# SkyNetV3main-1.net
KiCad netlist of a schematic drawn in EAGLE
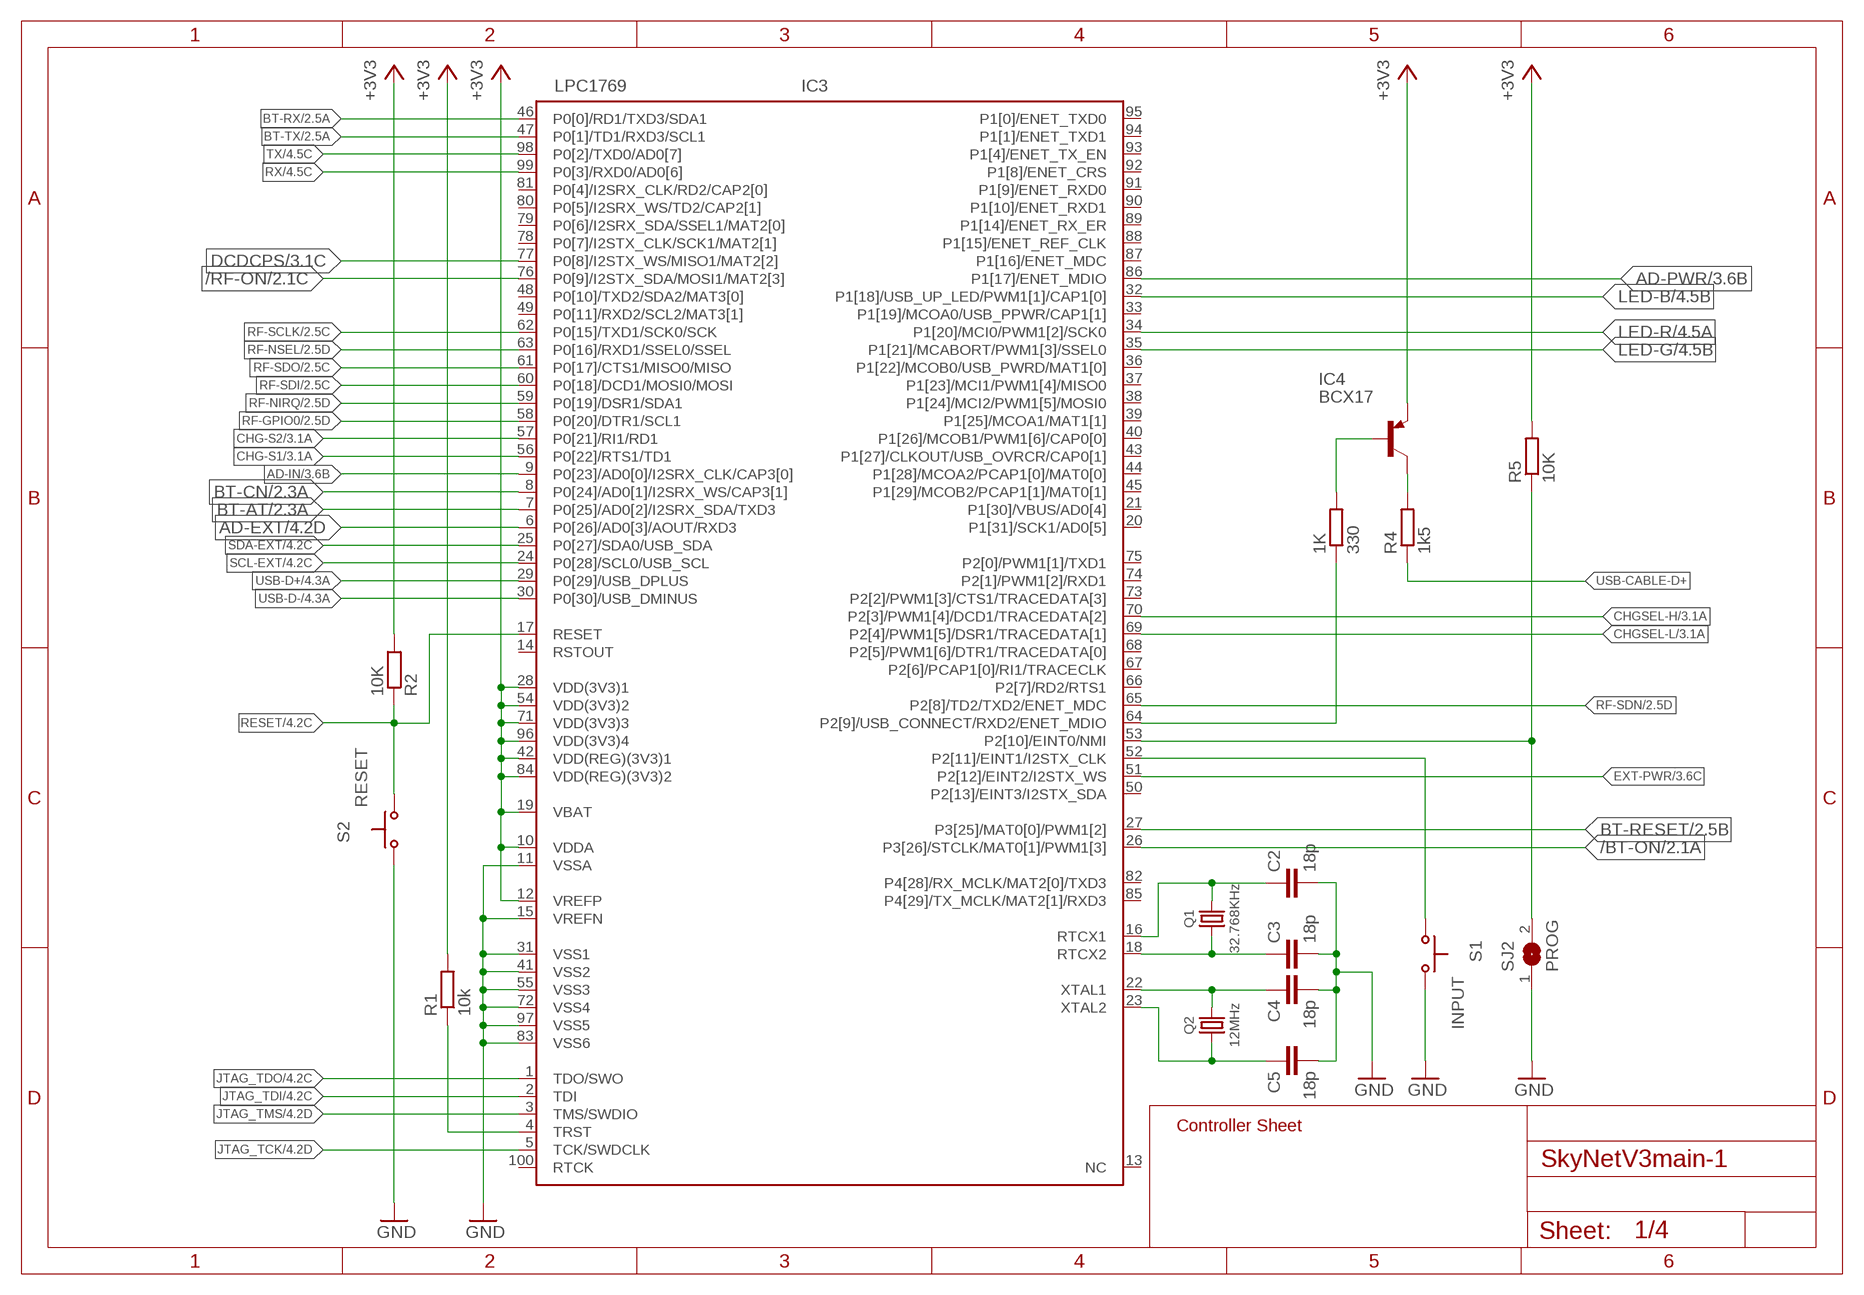
[diagram p0: schematic, sheet 1]
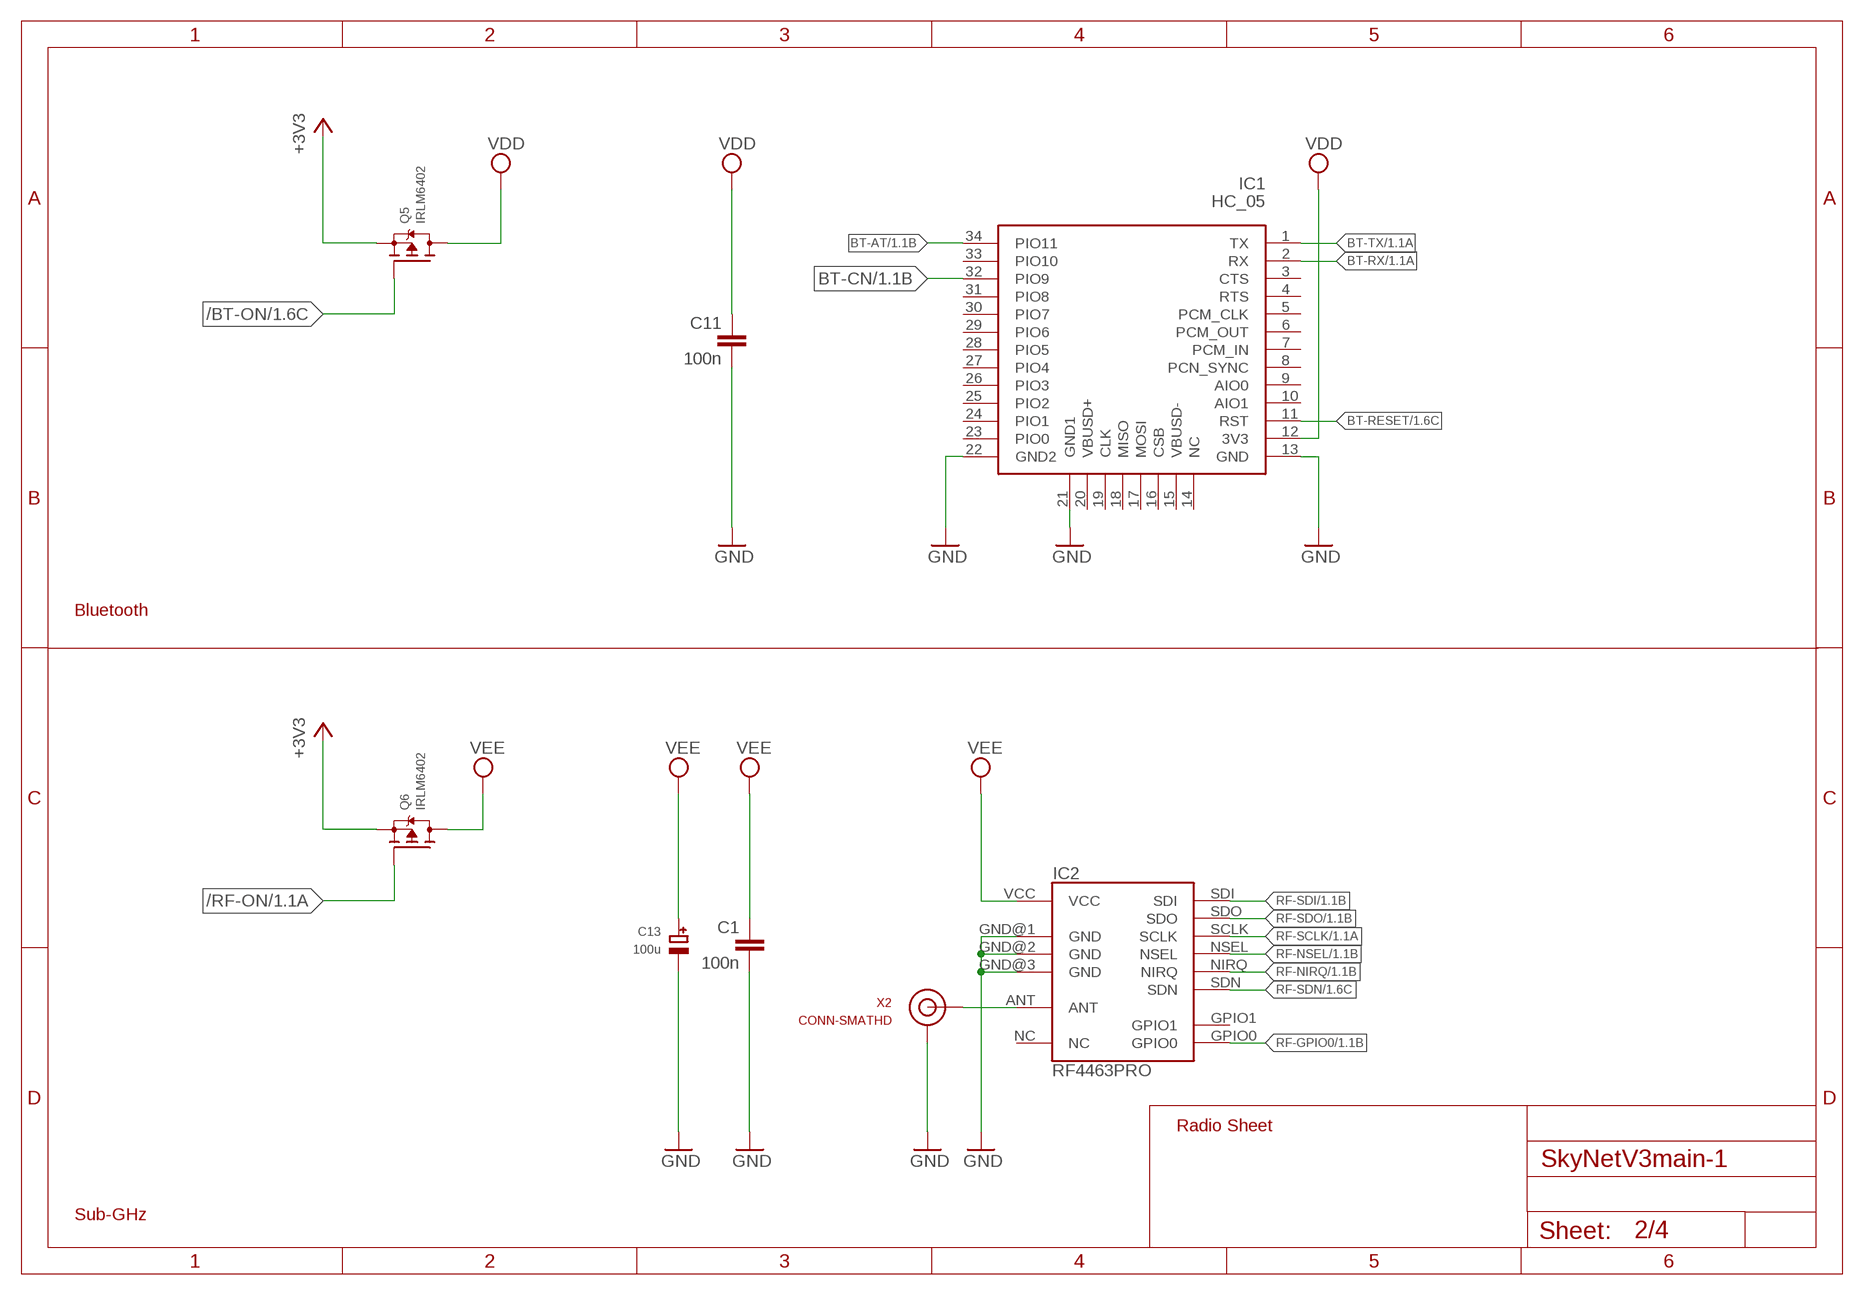
[diagram p1: schematic, sheet 2]
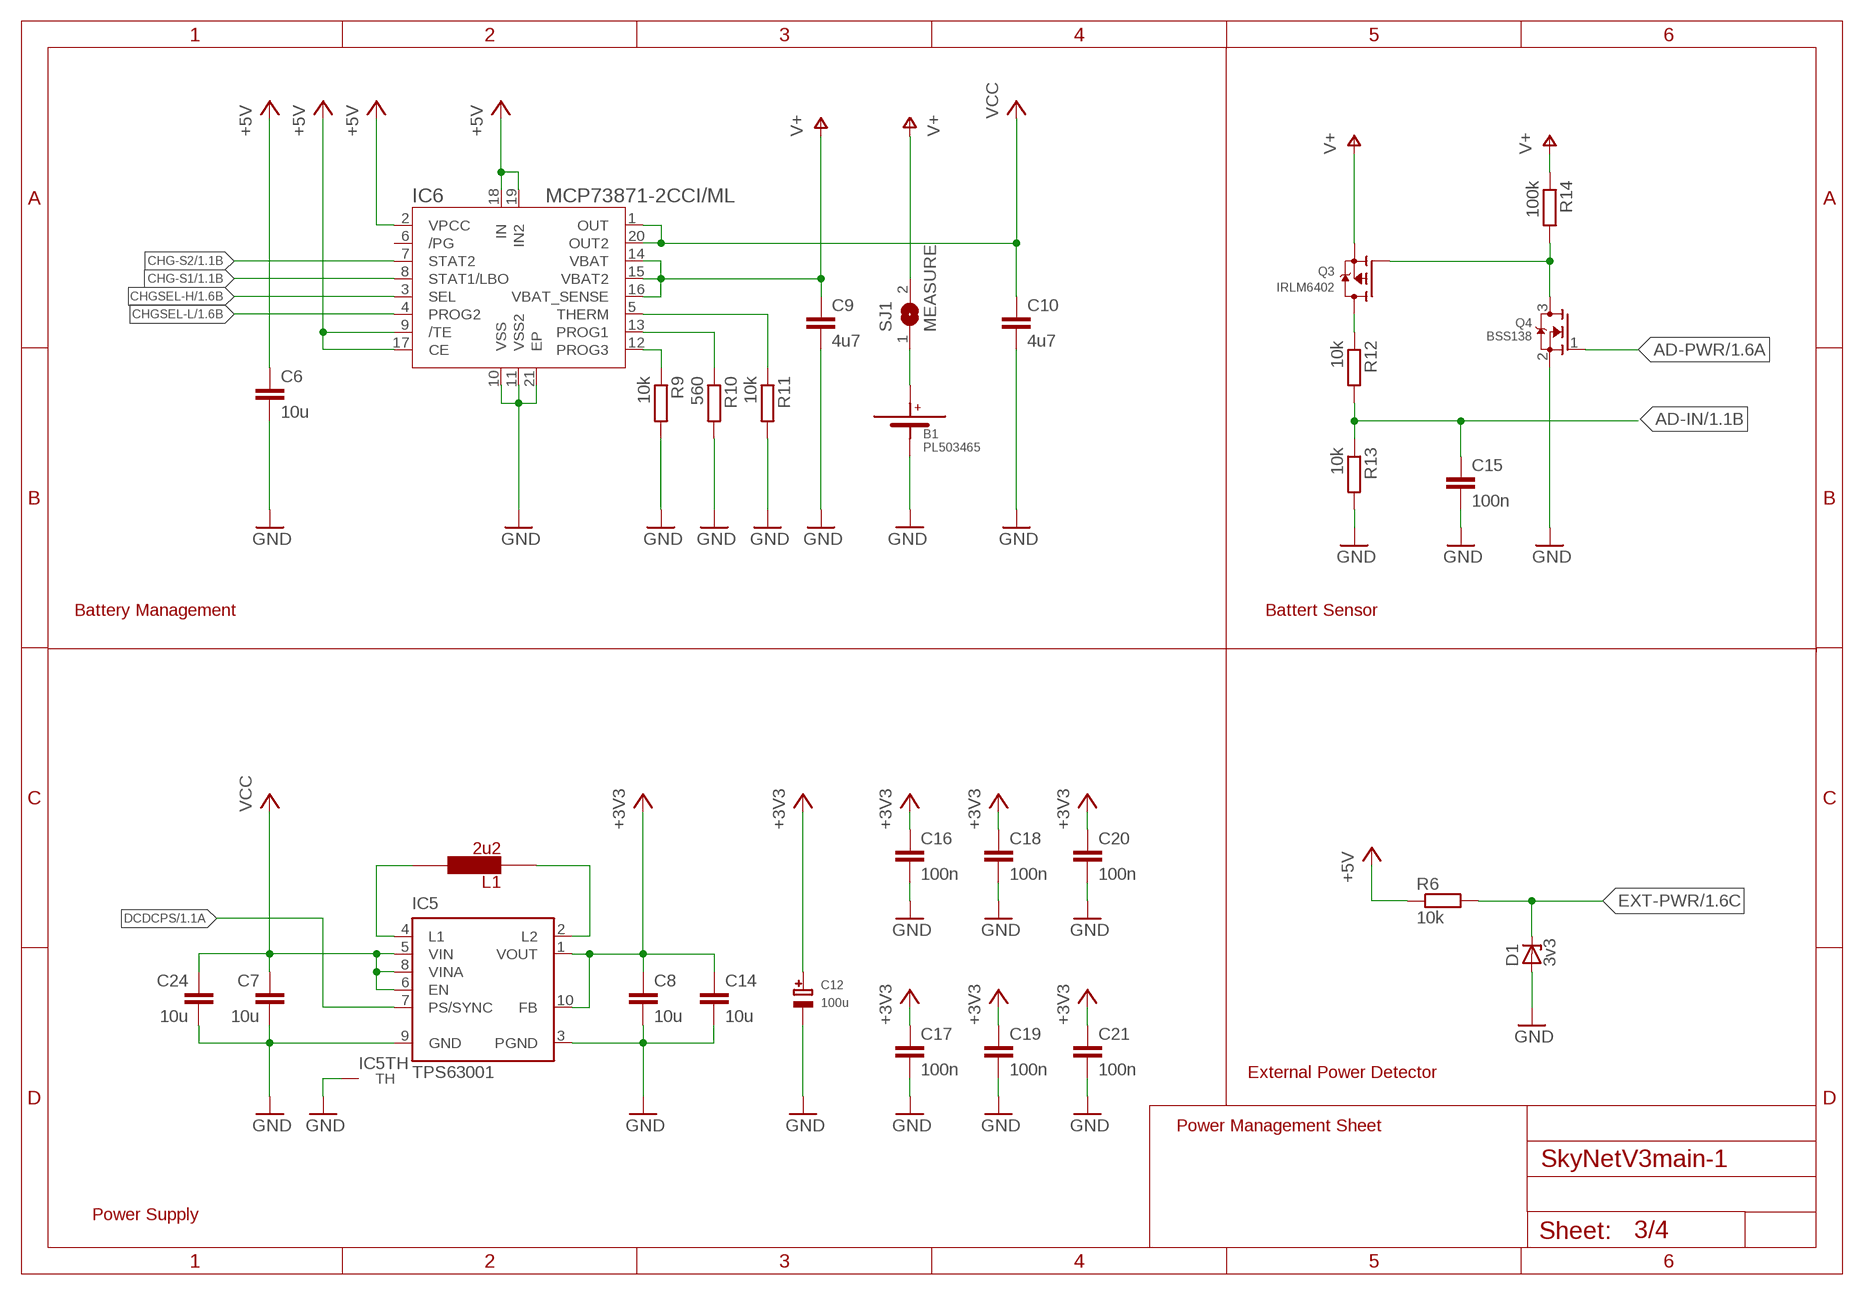
[diagram p2: schematic, sheet 3]
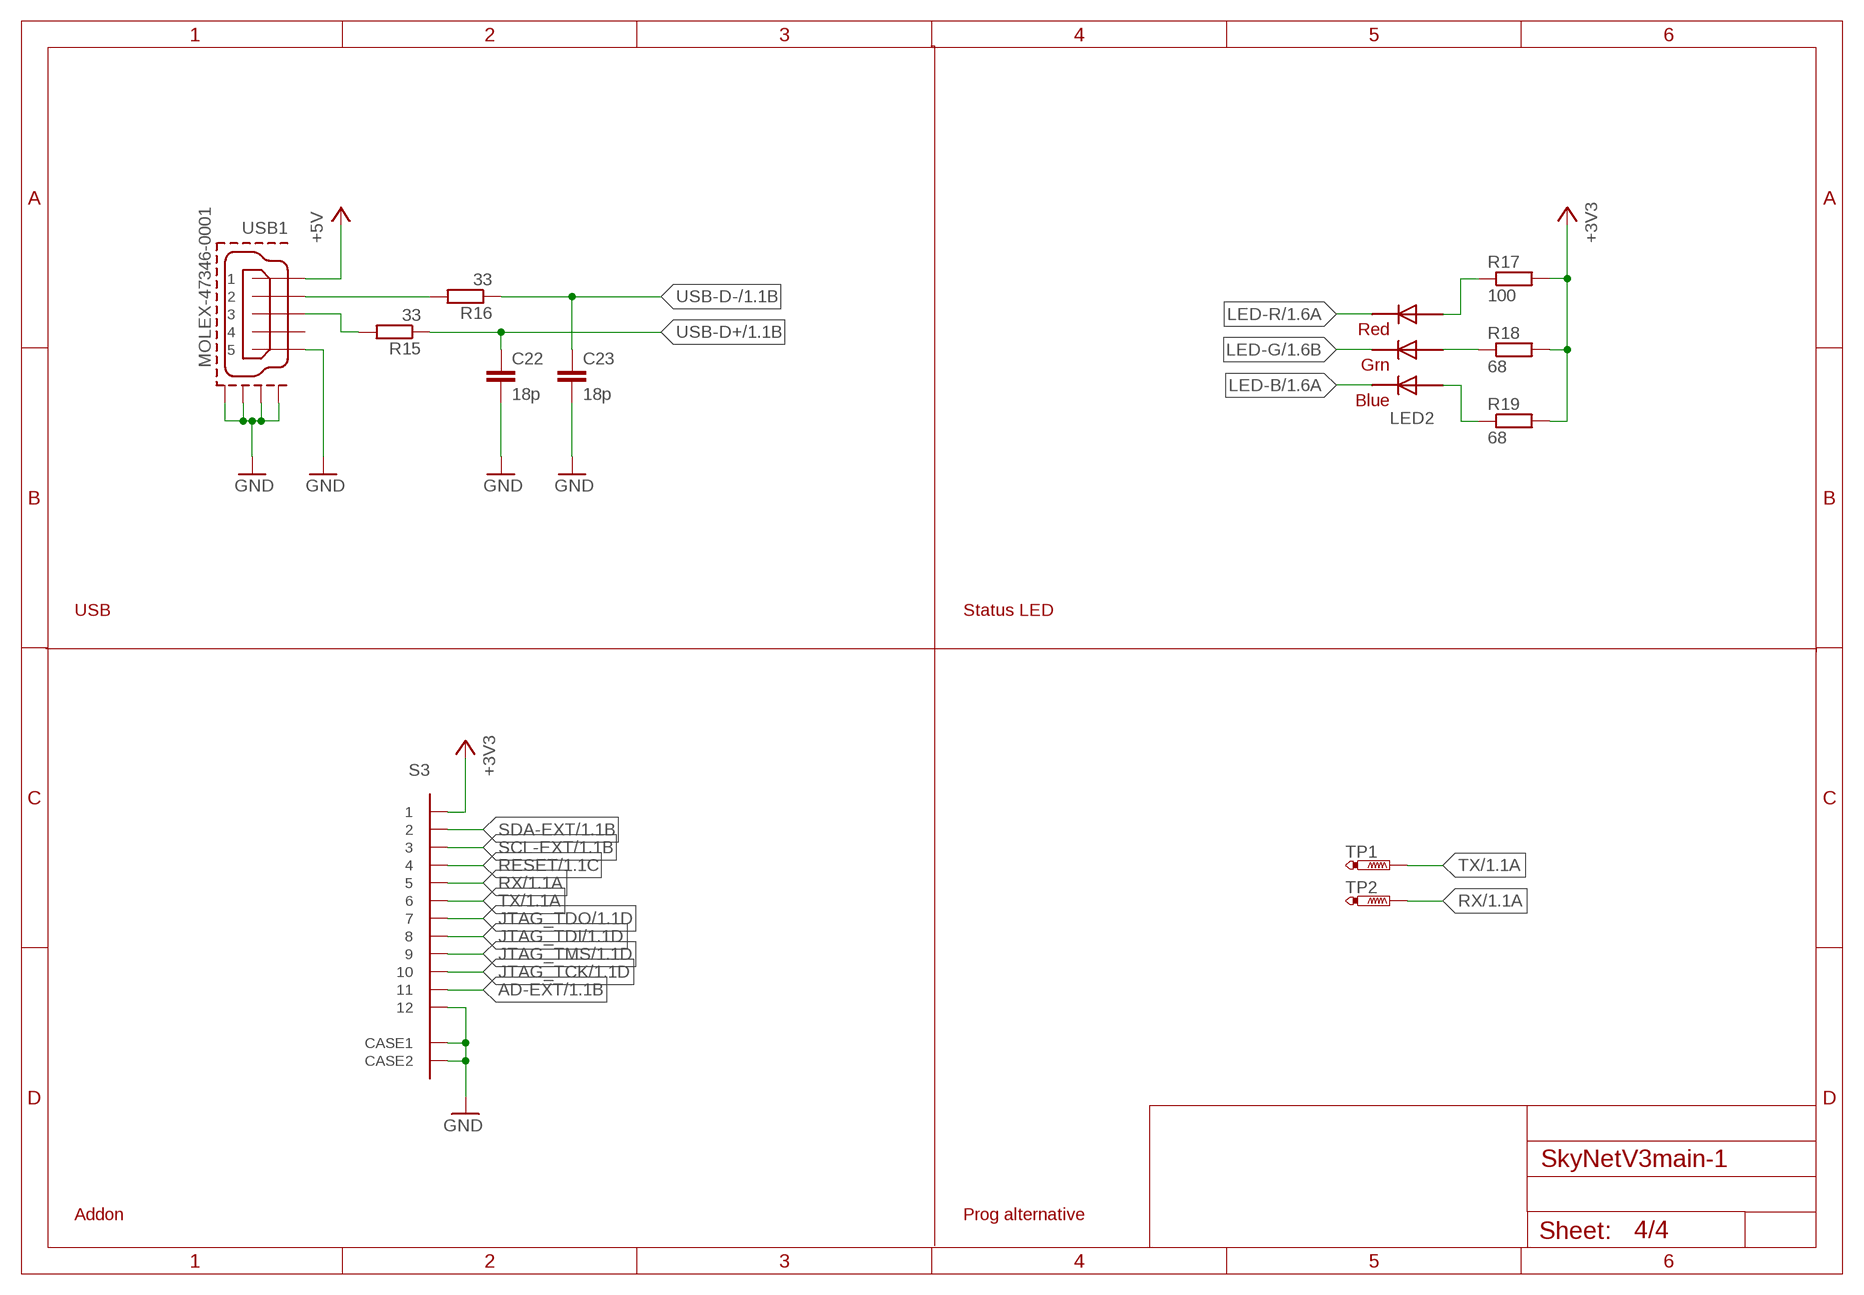
[diagram p3: schematic, sheet 4]

(export (version "E")
  (design (tool "Eeschema 10.0.6"))
  (components
    (comp (ref "1K")
      (value "330")
      (footprint "eagle-import:R0603")
      (libsource (lib "eagle-import") (part "R-EU_R0603"))
    )
    (comp (ref "C2")
      (value "18p")
      (footprint "eagle-import:C0603")
      (libsource (lib "eagle-import") (part "C-EUC0603"))
    )
    (comp (ref "C3")
      (value "18p")
      (footprint "eagle-import:C0603")
      (libsource (lib "eagle-import") (part "C-EUC0603"))
    )
    (comp (ref "C4")
      (value "18p")
      (footprint "eagle-import:C0603")
      (libsource (lib "eagle-import") (part "C-EUC0603"))
    )
    (comp (ref "C5")
      (value "18p")
      (footprint "eagle-import:C0603")
      (libsource (lib "eagle-import") (part "C-EUC0603"))
    )
    (comp (ref "IC3")
      (value "LPC1769")
      (footprint "eagle-import:LQFP100-14X14")
      (libsource (lib "eagle-import") (part "LPC1768"))
    )
    (comp (ref "IC4")
      (value "BCX17")
      (footprint "eagle-import:SOT23")
      (libsource (lib "eagle-import") (part "BCX17"))
    )
    (comp (ref "Q1")
      (value "32.768KHz")
      (footprint "eagle-import:XTAL_49_18")
      (libsource (lib "eagle-import") (part "XTAL2-PAD"))
    )
    (comp (ref "Q2")
      (value "12MHz")
      (footprint "eagle-import:XTAL_50_32")
      (libsource (lib "eagle-import") (part "XTAL4-PAD"))
    )
    (comp (ref "R1")
      (value "10k")
      (footprint "eagle-import:R0603")
      (libsource (lib "eagle-import") (part "R-EU_R0603"))
    )
    (comp (ref "R2")
      (value "10K")
      (footprint "eagle-import:R0603")
      (libsource (lib "eagle-import") (part "R-EU_R0603"))
    )
    (comp (ref "R4")
      (value "1k5")
      (footprint "eagle-import:R0603")
      (libsource (lib "eagle-import") (part "R-EU_R0603"))
    )
    (comp (ref "R5")
      (value "10K")
      (footprint "eagle-import:R0603")
      (libsource (lib "eagle-import") (part "R-EU_R0603"))
    )
    (comp (ref "S1")
      (value "INPUT")
      (footprint "eagle-import:PTS645-SMD")
      (libsource (lib "eagle-import") (part "PTS645S???SMTR"))
    )
    (comp (ref "S2")
      (value "RESET")
      (footprint "eagle-import:PTS645-SMD")
      (libsource (lib "eagle-import") (part "PTS645S???SMTR"))
    )
    (comp (ref "SJ2")
      (value "PROG")
      (footprint "eagle-import:SJ")
      (libsource (lib "eagle-import") (part "SJ"))
    )
    (comp (ref "B1")
      (value "PL503465")
      (footprint "eagle-import:PL503465")
      (libsource (lib "eagle-import") (part "1S"))
    )
    (comp (ref "C6")
      (value "10u")
      (footprint "eagle-import:C1206K")
      (libsource (lib "eagle-import") (part "C-EUC1206K"))
    )
    (comp (ref "C7")
      (value "10u")
      (footprint "eagle-import:C1206K")
      (libsource (lib "eagle-import") (part "C-EUC1206K"))
    )
    (comp (ref "C8")
      (value "10u")
      (footprint "eagle-import:C1206K")
      (libsource (lib "eagle-import") (part "C-EUC1206K"))
    )
    (comp (ref "C9")
      (value "4u7")
      (footprint "eagle-import:C1206K")
      (libsource (lib "eagle-import") (part "C-EUC1206K"))
    )
    (comp (ref "C10")
      (value "4u7")
      (footprint "eagle-import:C1206K")
      (libsource (lib "eagle-import") (part "C-EUC1206K"))
    )
    (comp (ref "C12")
      (value "100u")
      (footprint "eagle-import:EIA6032-28_C-W")
      (libsource (lib "eagle-import") (part "CAP_TANTALUMC/6032_WAVE"))
    )
    (comp (ref "C14")
      (value "10u")
      (footprint "eagle-import:C1206K")
      (libsource (lib "eagle-import") (part "C-EUC1206K"))
    )
    (comp (ref "C15")
      (value "100n")
      (footprint "eagle-import:C0603")
      (libsource (lib "eagle-import") (part "C-EUC0603"))
    )
    (comp (ref "C16")
      (value "100n")
      (footprint "eagle-import:C0603")
      (libsource (lib "eagle-import") (part "C-EUC0603"))
    )
    (comp (ref "C17")
      (value "100n")
      (footprint "eagle-import:C0603")
      (libsource (lib "eagle-import") (part "C-EUC0603"))
    )
    (comp (ref "C18")
      (value "100n")
      (footprint "eagle-import:C0603")
      (libsource (lib "eagle-import") (part "C-EUC0603"))
    )
    (comp (ref "C19")
      (value "100n")
      (footprint "eagle-import:C0603")
      (libsource (lib "eagle-import") (part "C-EUC0603"))
    )
    (comp (ref "C20")
      (value "100n")
      (footprint "eagle-import:C0603")
      (libsource (lib "eagle-import") (part "C-EUC0603"))
    )
    (comp (ref "C21")
      (value "100n")
      (footprint "eagle-import:C0603")
      (libsource (lib "eagle-import") (part "C-EUC0603"))
    )
    (comp (ref "C24")
      (value "10u")
      (footprint "eagle-import:C1206K")
      (libsource (lib "eagle-import") (part "C-EUC1206K"))
    )
    (comp (ref "D1")
      (value "3v3")
      (footprint "eagle-import:SOT23")
      (libsource (lib "eagle-import") (part "ZENER-DIODESOT23"))
    )
    (comp (ref "IC5")
      (value "TPS63001")
      (footprint "eagle-import:DRC-S-PVSON-N10")
      (fields (field (name "MPN") "TPS63000DRCTG4"))
      (libsource (lib "eagle-import") (part "TPS6300"))
    )
    (comp (ref "IC6")
      (value "MCP73871-2CCI/ML")
      (footprint "eagle-import:QFN20-4X4")
      (libsource (lib "eagle-import") (part "MCP73871ML-2CCI/"))
    )
    (comp (ref "L1")
      (value "2u2")
      (footprint "eagle-import:LPS4012")
      (libsource (lib "eagle-import") (part "LPS4012"))
    )
    (comp (ref "Q3")
      (value "IRLM6402")
      (footprint "eagle-import:SOT23-WIDE")
      (libsource (lib "eagle-import") (part "MOSFET-PWIDE"))
    )
    (comp (ref "Q4")
      (value "BSS138")
      (footprint "eagle-import:SOT23-WIDE")
      (libsource (lib "eagle-import") (part "MOSFET-NWIDE"))
    )
    (comp (ref "R6")
      (value "10k")
      (footprint "eagle-import:R0603")
      (libsource (lib "eagle-import") (part "R-EU_R0603"))
    )
    (comp (ref "R9")
      (value "10k")
      (footprint "eagle-import:R0603")
      (libsource (lib "eagle-import") (part "R-EU_R0603"))
    )
    (comp (ref "R10")
      (value "560")
      (footprint "eagle-import:R0603")
      (libsource (lib "eagle-import") (part "R-EU_R0603"))
    )
    (comp (ref "R11")
      (value "10k")
      (footprint "eagle-import:R0603")
      (libsource (lib "eagle-import") (part "R-EU_R0603"))
    )
    (comp (ref "R12")
      (value "10k")
      (footprint "eagle-import:R0603")
      (libsource (lib "eagle-import") (part "R-EU_R0603"))
    )
    (comp (ref "R13")
      (value "10k")
      (footprint "eagle-import:R0603")
      (libsource (lib "eagle-import") (part "R-EU_R0603"))
    )
    (comp (ref "R14")
      (value "100k")
      (footprint "eagle-import:R0603")
      (libsource (lib "eagle-import") (part "R-EU_R0603"))
    )
    (comp (ref "SJ1")
      (value "MEASURE")
      (footprint "eagle-import:SJ")
      (libsource (lib "eagle-import") (part "SJ"))
    )
    (comp (ref "C1")
      (value "100n")
      (footprint "eagle-import:C1206K")
      (libsource (lib "eagle-import") (part "C-EUC1206K"))
    )
    (comp (ref "C11")
      (value "100n")
      (footprint "eagle-import:C1206K")
      (libsource (lib "eagle-import") (part "C-EUC1206K"))
    )
    (comp (ref "C13")
      (value "100u")
      (footprint "eagle-import:EIA6032-28_C-W")
      (libsource (lib "eagle-import") (part "CAP_TANTALUMC/6032_WAVE"))
    )
    (comp (ref "IC1")
      (value "HC_05")
      (footprint "eagle-import:BLUETOOTH_SMD")
      (libsource (lib "eagle-import") (part "HC_05"))
    )
    (comp (ref "IC2")
      (value "RF4463PRO")
      (footprint "eagle-import:STD_BOARD")
      (libsource (lib "eagle-import") (part "RF4463PRO"))
    )
    (comp (ref "Q5")
      (value "IRLM6402")
      (footprint "eagle-import:SOT23-WIDE")
      (libsource (lib "eagle-import") (part "MOSFET-PWIDE"))
    )
    (comp (ref "Q6")
      (value "IRLM6402")
      (footprint "eagle-import:SOT23-WIDE")
      (libsource (lib "eagle-import") (part "MOSFET-PWIDE"))
    )
    (comp (ref "X2")
      (value "CONN-SMATHD")
      (footprint "eagle-import:SMA-THD")
      (libsource (lib "eagle-import") (part "CONN-SMATHD"))
    )
    (comp (ref "C22")
      (value "18p")
      (footprint "eagle-import:C0603")
      (libsource (lib "eagle-import") (part "C-EUC0603"))
    )
    (comp (ref "C23")
      (value "18p")
      (footprint "eagle-import:C0603")
      (libsource (lib "eagle-import") (part "C-EUC0603"))
    )
    (comp (ref "LED2")
      (value "RGBLED5050")
      (footprint "eagle-import:RGBLED5050")
      (libsource (lib "eagle-import") (part "RGBLED5050"))
    )
    (comp (ref "R15")
      (value "33")
      (footprint "eagle-import:R0603")
      (libsource (lib "eagle-import") (part "R-EU_R0603"))
    )
    (comp (ref "R16")
      (value "33")
      (footprint "eagle-import:R0603")
      (libsource (lib "eagle-import") (part "R-EU_R0603"))
    )
    (comp (ref "R17")
      (value "100")
      (footprint "eagle-import:R0603")
      (libsource (lib "eagle-import") (part "R-EU_R0603"))
    )
    (comp (ref "R18")
      (value "68")
      (footprint "eagle-import:R0603")
      (libsource (lib "eagle-import") (part "R-EU_R0603"))
    )
    (comp (ref "R19")
      (value "68")
      (footprint "eagle-import:R0603")
      (libsource (lib "eagle-import") (part "R-EU_R0603"))
    )
    (comp (ref "S3")
      (value "MOLEX-52892-1233")
      (footprint "eagle-import:MOLEX-52892-1233")
      (libsource (lib "eagle-import") (part "MOLEX-52892-1233"))
    )
    (comp (ref "TP1")
      (value "PTR1B1,27")
      (footprint "eagle-import:B1,27")
      (libsource (lib "eagle-import") (part "PTR1B1,27"))
    )
    (comp (ref "TP2")
      (value "PTR1B1,27")
      (footprint "eagle-import:B1,27")
      (libsource (lib "eagle-import") (part "PTR1B1,27"))
    )
    (comp (ref "USB1")
      (value "MOLEX-47346-0001")
      (footprint "eagle-import:MOLEX-47364-0001")
      (libsource (lib "eagle-import") (part "MOLEX-47346-0001"))
    )
  )
  (nets
    (net (code "1") (name "+3V3") (class "Default")
      (node (ref "C12") (pin "+") (pinfunction "+_+") (pintype "passive"))
      (node (ref "C14") (pin "1") (pinfunction "1_1") (pintype "passive"))
      (node (ref "C16") (pin "1") (pinfunction "1_1") (pintype "passive"))
      (node (ref "C17") (pin "1") (pinfunction "1_1") (pintype "passive"))
      (node (ref "C18") (pin "1") (pinfunction "1_1") (pintype "passive"))
      (node (ref "C19") (pin "1") (pinfunction "1_1") (pintype "passive"))
      (node (ref "C20") (pin "1") (pinfunction "1_1") (pintype "passive"))
      (node (ref "C21") (pin "1") (pinfunction "1_1") (pintype "passive"))
      (node (ref "C8") (pin "1") (pinfunction "1_1") (pintype "passive"))
      (node (ref "IC3") (pin "10") (pinfunction "VDDA_10") (pintype "bidirectional"))
      (node (ref "IC3") (pin "12") (pinfunction "VREFP_12") (pintype "bidirectional"))
      (node (ref "IC3") (pin "19") (pinfunction "VBAT_19") (pintype "bidirectional"))
      (node (ref "IC3") (pin "28") (pinfunction "VDD(3V3)1_28") (pintype "bidirectional"))
      (node (ref "IC3") (pin "42") (pinfunction "VDD(REG)(3V3)1_42") (pintype "bidirectional"))
      (node (ref "IC3") (pin "54") (pinfunction "VDD(3V3)2_54") (pintype "bidirectional"))
      (node (ref "IC3") (pin "71") (pinfunction "VDD(3V3)3_71") (pintype "bidirectional"))
      (node (ref "IC3") (pin "84") (pinfunction "VDD(REG)(3V3)2_84") (pintype "bidirectional"))
      (node (ref "IC3") (pin "96") (pinfunction "VDD(3V3)4_96") (pintype "bidirectional"))
      (node (ref "IC4") (pin "2") (pinfunction "E_2") (pintype "passive"))
      (node (ref "IC5") (pin "1") (pinfunction "VOUT_1") (pintype "output"))
      (node (ref "IC5") (pin "10") (pinfunction "FB_10") (pintype "input"))
      (node (ref "Q5") (pin "2") (pinfunction "S_2") (pintype "passive"))
      (node (ref "Q6") (pin "2") (pinfunction "S_2") (pintype "passive"))
      (node (ref "R1") (pin "2") (pinfunction "2_2") (pintype "passive"))
      (node (ref "R17") (pin "2") (pinfunction "2_2") (pintype "passive"))
      (node (ref "R18") (pin "2") (pinfunction "2_2") (pintype "passive"))
      (node (ref "R19") (pin "2") (pinfunction "2_2") (pintype "passive"))
      (node (ref "R2") (pin "2") (pinfunction "2_2") (pintype "passive"))
      (node (ref "R5") (pin "2") (pinfunction "2_2") (pintype "passive"))
      (node (ref "S3") (pin "P$1") (pinfunction "1_P$1") (pintype "bidirectional"))
    )
    (net (code "2") (name "+5V") (class "Default")
      (node (ref "C6") (pin "1") (pinfunction "1_1") (pintype "passive"))
      (node (ref "IC6") (pin "17") (pinfunction "CE_17") (pintype "input"))
      (node (ref "IC6") (pin "18") (pinfunction "IN_18") (pintype "power_in"))
      (node (ref "IC6") (pin "19") (pinfunction "IN2_19") (pintype "power_in"))
      (node (ref "IC6") (pin "2") (pinfunction "VPCC_2") (pintype "input"))
      (node (ref "IC6") (pin "9") (pinfunction "/TE_9") (pintype "input"))
      (node (ref "R6") (pin "1") (pinfunction "1_1") (pintype "passive"))
      (node (ref "USB1") (pin "1") (pinfunction "1_1") (pintype "input"))
    )
    (net (code "3") (name "AD-EXT") (class "Default")
      (node (ref "IC3") (pin "6") (pinfunction "P0[26]/AD0[3]/AOUT/RXD3_6") (pintype "bidirectional"))
      (node (ref "S3") (pin "P$11") (pinfunction "11_P$11") (pintype "bidirectional"))
    )
    (net (code "4") (name "AD-IN") (class "Default")
      (node (ref "C15") (pin "1") (pinfunction "1_1") (pintype "passive"))
      (node (ref "IC3") (pin "9") (pinfunction "P0[23]/AD0[0]/I2SRX_CLK/CAP3[0]_9") (pintype "bidirectional"))
      (node (ref "R12") (pin "2") (pinfunction "2_2") (pintype "passive"))
      (node (ref "R13") (pin "1") (pinfunction "1_1") (pintype "passive"))
    )
    (net (code "5") (name "AD-PWR") (class "Default")
      (node (ref "IC3") (pin "86") (pinfunction "P1[17]/ENET_MDIO_86") (pintype "bidirectional"))
      (node (ref "Q4") (pin "1") (pinfunction "G_1") (pintype "bidirectional"))
    )
    (net (code "6") (name "BT-AT") (class "Default")
      (node (ref "IC1") (pin "34") (pinfunction "PIO11_34") (pintype "bidirectional"))
      (node (ref "IC3") (pin "7") (pinfunction "P0[25]/AD0[2]/I2SRX_SDA/TXD3_7") (pintype "bidirectional"))
    )
    (net (code "7") (name "BT-CN") (class "Default")
      (node (ref "IC1") (pin "32") (pinfunction "PIO9_32") (pintype "bidirectional"))
      (node (ref "IC3") (pin "8") (pinfunction "P0[24]/AD0[1]/I2SRX_WS/CAP3[1]_8") (pintype "bidirectional"))
    )
    (net (code "8") (name "BT-RESET") (class "Default")
      (node (ref "IC1") (pin "11") (pinfunction "RST_11") (pintype "bidirectional"))
      (node (ref "IC3") (pin "27") (pinfunction "P3[25]/MAT0[0]/PWM1[2]_27") (pintype "bidirectional"))
    )
    (net (code "9") (name "BT-RX") (class "Default")
      (node (ref "IC1") (pin "2") (pinfunction "RX_2") (pintype "bidirectional"))
      (node (ref "IC3") (pin "46") (pinfunction "P0[0]/RD1/TXD3/SDA1_46") (pintype "bidirectional"))
    )
    (net (code "10") (name "BT-TX") (class "Default")
      (node (ref "IC1") (pin "1") (pinfunction "TX_1") (pintype "bidirectional"))
      (node (ref "IC3") (pin "47") (pinfunction "P0[1]/TD1/RXD3/SCL1_47") (pintype "bidirectional"))
    )
    (net (code "11") (name "CHG-S1") (class "Default")
      (node (ref "IC3") (pin "56") (pinfunction "P0[22]/RTS1/TD1_56") (pintype "bidirectional"))
      (node (ref "IC6") (pin "8") (pinfunction "STAT1/LBO_8") (pintype "open_collector"))
    )
    (net (code "12") (name "CHG-S2") (class "Default")
      (node (ref "IC3") (pin "57") (pinfunction "P0[21]/RI1/RD1_57") (pintype "bidirectional"))
      (node (ref "IC6") (pin "7") (pinfunction "STAT2_7") (pintype "open_collector"))
    )
    (net (code "13") (name "CHGSEL-H") (class "Default")
      (node (ref "IC3") (pin "70") (pinfunction "P2[3]/PWM1[4]/DCD1/TRACEDATA[2]_70") (pintype "bidirectional"))
      (node (ref "IC6") (pin "3") (pinfunction "SEL_3") (pintype "input"))
    )
    (net (code "14") (name "CHGSEL-L") (class "Default")
      (node (ref "IC3") (pin "69") (pinfunction "P2[4]/PWM1[5]/DSR1/TRACEDATA[1]_69") (pintype "bidirectional"))
      (node (ref "IC6") (pin "4") (pinfunction "PROG2_4") (pintype "input"))
    )
    (net (code "15") (name "DCDCPS") (class "Default")
      (node (ref "IC3") (pin "77") (pinfunction "P0[8]/I2STX_WS/MISO1/MAT2[2]_77") (pintype "bidirectional"))
      (node (ref "IC5") (pin "7") (pinfunction "PS/SYNC_7") (pintype "input"))
    )
    (net (code "16") (name "EXT-PWR") (class "Default")
      (node (ref "D1") (pin "3") (pinfunction "C_3") (pintype "passive"))
      (node (ref "IC3") (pin "51") (pinfunction "P2[12]/EINT2/I2STX_WS_51") (pintype "bidirectional"))
      (node (ref "R6") (pin "2") (pinfunction "2_2") (pintype "passive"))
    )
    (net (code "17") (name "GND") (class "Default")
      (node (ref "B1") (pin "P-") (pinfunction "P-_P-") (pintype "bidirectional"))
      (node (ref "C1") (pin "2") (pinfunction "2_2") (pintype "passive"))
      (node (ref "C10") (pin "2") (pinfunction "2_2") (pintype "passive"))
      (node (ref "C11") (pin "2") (pinfunction "2_2") (pintype "passive"))
      (node (ref "C12") (pin "-") (pinfunction "-_-") (pintype "passive"))
      (node (ref "C13") (pin "-") (pinfunction "-_-") (pintype "passive"))
      (node (ref "C14") (pin "2") (pinfunction "2_2") (pintype "passive"))
      (node (ref "C15") (pin "2") (pinfunction "2_2") (pintype "passive"))
      (node (ref "C16") (pin "2") (pinfunction "2_2") (pintype "passive"))
      (node (ref "C17") (pin "2") (pinfunction "2_2") (pintype "passive"))
      (node (ref "C18") (pin "2") (pinfunction "2_2") (pintype "passive"))
      (node (ref "C19") (pin "2") (pinfunction "2_2") (pintype "passive"))
      (node (ref "C2") (pin "2") (pinfunction "2_2") (pintype "passive"))
      (node (ref "C20") (pin "2") (pinfunction "2_2") (pintype "passive"))
      (node (ref "C21") (pin "2") (pinfunction "2_2") (pintype "passive"))
      (node (ref "C22") (pin "2") (pinfunction "2_2") (pintype "passive"))
      (node (ref "C23") (pin "2") (pinfunction "2_2") (pintype "passive"))
      (node (ref "C24") (pin "2") (pinfunction "2_2") (pintype "passive"))
      (node (ref "C3") (pin "2") (pinfunction "2_2") (pintype "passive"))
      (node (ref "C4") (pin "2") (pinfunction "2_2") (pintype "passive"))
      (node (ref "C5") (pin "2") (pinfunction "2_2") (pintype "passive"))
      (node (ref "C6") (pin "2") (pinfunction "2_2") (pintype "passive"))
      (node (ref "C7") (pin "2") (pinfunction "2_2") (pintype "passive"))
      (node (ref "C8") (pin "2") (pinfunction "2_2") (pintype "passive"))
      (node (ref "C9") (pin "2") (pinfunction "2_2") (pintype "passive"))
      (node (ref "D1") (pin "1") (pinfunction "A_1") (pintype "passive"))
      (node (ref "IC1") (pin "13") (pinfunction "GND_13") (pintype "bidirectional"))
      (node (ref "IC1") (pin "21") (pinfunction "GND1_21") (pintype "bidirectional"))
      (node (ref "IC1") (pin "22") (pinfunction "GND2_22") (pintype "bidirectional"))
      (node (ref "IC2") (pin "GND@1") (pinfunction "GND_GND@1") (pintype "power_in"))
      (node (ref "IC2") (pin "GND@2") (pinfunction "GND_GND@2") (pintype "power_in"))
      (node (ref "IC2") (pin "GND@3") (pinfunction "GND_GND@3") (pintype "power_in"))
      (node (ref "IC3") (pin "11") (pinfunction "VSSA_11") (pintype "bidirectional"))
      (node (ref "IC3") (pin "15") (pinfunction "VREFN_15") (pintype "bidirectional"))
      (node (ref "IC3") (pin "31") (pinfunction "VSS1_31") (pintype "bidirectional"))
      (node (ref "IC3") (pin "41") (pinfunction "VSS2_41") (pintype "bidirectional"))
      (node (ref "IC3") (pin "55") (pinfunction "VSS3_55") (pintype "bidirectional"))
      (node (ref "IC3") (pin "72") (pinfunction "VSS4_72") (pintype "bidirectional"))
      (node (ref "IC3") (pin "83") (pinfunction "VSS6_83") (pintype "bidirectional"))
      (node (ref "IC3") (pin "97") (pinfunction "VSS5_97") (pintype "bidirectional"))
      (node (ref "IC5") (pin "3") (pinfunction "PGND_3") (pintype "power_in"))
      (node (ref "IC5") (pin "9") (pinfunction "GND_9") (pintype "power_in"))
      (node (ref "IC5") (pin "TH") (pinfunction "TH_TH") (pintype "passive"))
      (node (ref "IC6") (pin "10") (pinfunction "VSS_10") (pintype "power_in"))
      (node (ref "IC6") (pin "11") (pinfunction "VSS2_11") (pintype "power_in"))
      (node (ref "IC6") (pin "21") (pinfunction "EP_21") (pintype "power_in"))
      (node (ref "Q4") (pin "2") (pinfunction "S_2") (pintype "bidirectional"))
      (node (ref "R10") (pin "2") (pinfunction "2_2") (pintype "passive"))
      (node (ref "R11") (pin "2") (pinfunction "2_2") (pintype "passive"))
      (node (ref "R13") (pin "2") (pinfunction "2_2") (pintype "passive"))
      (node (ref "R9") (pin "2") (pinfunction "2_2") (pintype "passive"))
      (node (ref "S1") (pin "3") (pinfunction "S_3") (pintype "passive"))
      (node (ref "S1") (pin "4") (pinfunction "S_4") (pintype "passive"))
      (node (ref "S2") (pin "1") (pinfunction "P_1") (pintype "passive"))
      (node (ref "S2") (pin "2") (pinfunction "P_2") (pintype "passive"))
      (node (ref "S3") (pin "P$12") (pinfunction "12_P$12") (pintype "bidirectional"))
      (node (ref "S3") (pin "P$GND1") (pinfunction "CASE1_P$GND1") (pintype "bidirectional"))
      (node (ref "S3") (pin "P$GND2") (pinfunction "CASE2_P$GND2") (pintype "bidirectional"))
      (node (ref "SJ2") (pin "1") (pinfunction "1_1") (pintype "passive"))
      (node (ref "USB1") (pin "5") (pinfunction "5_5") (pintype "input"))
      (node (ref "USB1") (pin "GND1") (pinfunction "GND1_GND1") (pintype "bidirectional"))
      (node (ref "USB1") (pin "GND2") (pinfunction "GND2_GND2") (pintype "bidirectional"))
      (node (ref "USB1") (pin "GND3") (pinfunction "GND3_GND3") (pintype "bidirectional"))
      (node (ref "USB1") (pin "GND4") (pinfunction "GND4_GND4") (pintype "bidirectional"))
      (node (ref "X2") (pin "GND@0") (pinfunction "GND_GND@0") (pintype "bidirectional"))
      (node (ref "X2") (pin "GND@1") (pinfunction "GND_GND@1") (pintype "bidirectional"))
      (node (ref "X2") (pin "GND@2") (pinfunction "GND_GND@2") (pintype "bidirectional"))
      (node (ref "X2") (pin "GND@3") (pinfunction "GND_GND@3") (pintype "bidirectional"))
    )
    (net (code "18") (name "JTAG_TCK") (class "Default")
      (node (ref "IC3") (pin "5") (pinfunction "TCK/SWDCLK_5") (pintype "bidirectional"))
      (node (ref "S3") (pin "P$10") (pinfunction "10_P$10") (pintype "bidirectional"))
    )
    (net (code "19") (name "JTAG_TDI") (class "Default")
      (node (ref "IC3") (pin "2") (pinfunction "TDI_2") (pintype "bidirectional"))
      (node (ref "S3") (pin "P$8") (pinfunction "8_P$8") (pintype "bidirectional"))
    )
    (net (code "20") (name "JTAG_TDO") (class "Default")
      (node (ref "IC3") (pin "1") (pinfunction "TDO/SWO_1") (pintype "bidirectional"))
      (node (ref "S3") (pin "P$7") (pinfunction "7_P$7") (pintype "bidirectional"))
    )
    (net (code "21") (name "JTAG_TMS") (class "Default")
      (node (ref "IC3") (pin "3") (pinfunction "TMS/SWDIO_3") (pintype "bidirectional"))
      (node (ref "S3") (pin "P$9") (pinfunction "9_P$9") (pintype "bidirectional"))
    )
    (net (code "22") (name "LED-B") (class "Default")
      (node (ref "IC3") (pin "32") (pinfunction "P1[18]/USB_UP_LED/PWM1[1]/CAP1[0]_32") (pintype "bidirectional"))
      (node (ref "LED2") (pin "4") (pinfunction "BLUE_C_4") (pintype "bidirectional"))
    )
    (net (code "23") (name "LED-G") (class "Default")
      (node (ref "IC3") (pin "35") (pinfunction "P1[21]/MCABORT/PWM1[3]/SSEL0_35") (pintype "bidirectional"))
      (node (ref "LED2") (pin "6") (pinfunction "GREEN_C_6") (pintype "bidirectional"))
    )
    (net (code "24") (name "LED-R") (class "Default")
      (node (ref "IC3") (pin "34") (pinfunction "P1[20]/MCI0/PWM1[2]/SCK0_34") (pintype "bidirectional"))
      (node (ref "LED2") (pin "5") (pinfunction "RED_C_5") (pintype "bidirectional"))
    )
    (net (code "25") (name "Net-(B1-PadP+)") (class "Default")
      (node (ref "B1") (pin "P+") (pinfunction "P+_P+") (pintype "bidirectional"))
      (node (ref "SJ1") (pin "1") (pinfunction "1_1") (pintype "passive"))
    )
    (net (code "26") (name "Net-(IC3-P2[9]{slash}USB_CONNECT{slash}RXD2{slash}ENET_MDIO)") (class "Default")
      (node (ref "1K") (pin "1") (pinfunction "1_1") (pintype "passive"))
      (node (ref "IC3") (pin "64") (pinfunction "P2[9]/USB_CONNECT/RXD2/ENET_MDIO_64") (pintype "bidirectional"))
    )
    (net (code "27") (name "Net-(IC3-P2[10]{slash}EINT0{slash}NMI)") (class "Default")
      (node (ref "IC3") (pin "53") (pinfunction "P2[10]/EINT0/NMI_53") (pintype "bidirectional"))
      (node (ref "R5") (pin "1") (pinfunction "1_1") (pintype "passive"))
      (node (ref "SJ2") (pin "2") (pinfunction "2_2") (pintype "passive"))
    )
    (net (code "28") (name "Net-(IC3-P2[11]{slash}EINT1{slash}I2STX_CLK)") (class "Default")
      (node (ref "IC3") (pin "52") (pinfunction "P2[11]/EINT1/I2STX_CLK_52") (pintype "bidirectional"))
      (node (ref "S1") (pin "1") (pinfunction "P_1") (pintype "passive"))
      (node (ref "S1") (pin "2") (pinfunction "P_2") (pintype "passive"))
    )
    (net (code "29") (name "Net-(IC3-RTCX1)") (class "Default")
      (node (ref "C2") (pin "1") (pinfunction "1_1") (pintype "passive"))
      (node (ref "IC3") (pin "16") (pinfunction "RTCX1_16") (pintype "bidirectional"))
      (node (ref "Q1") (pin "2") (pinfunction "2_2") (pintype "passive"))
    )
    (net (code "30") (name "Net-(IC3-RTCX2)") (class "Default")
      (node (ref "C3") (pin "1") (pinfunction "1_1") (pintype "passive"))
      (node (ref "IC3") (pin "18") (pinfunction "RTCX2_18") (pintype "bidirectional"))
      (node (ref "Q1") (pin "1") (pinfunction "1_1") (pintype "passive"))
    )
    (net (code "31") (name "Net-(IC3-TRST)") (class "Default")
      (node (ref "IC3") (pin "4") (pinfunction "TRST_4") (pintype "bidirectional"))
      (node (ref "R1") (pin "1") (pinfunction "1_1") (pintype "passive"))
    )
    (net (code "32") (name "Net-(IC3-XTAL1)") (class "Default")
      (node (ref "C4") (pin "1") (pinfunction "1_1") (pintype "passive"))
      (node (ref "IC3") (pin "22") (pinfunction "XTAL1_22") (pintype "bidirectional"))
      (node (ref "Q2") (pin "3") (pinfunction "2_3") (pintype "passive"))
    )
    (net (code "33") (name "Net-(IC3-XTAL2)") (class "Default")
      (node (ref "C5") (pin "1") (pinfunction "1_1") (pintype "passive"))
      (node (ref "IC3") (pin "23") (pinfunction "XTAL2_23") (pintype "bidirectional"))
      (node (ref "Q2") (pin "1") (pinfunction "1_1") (pintype "passive"))
    )
    (net (code "34") (name "Net-(IC4-B)") (class "Default")
      (node (ref "1K") (pin "2") (pinfunction "2_2") (pintype "passive"))
      (node (ref "IC4") (pin "1") (pinfunction "B_1") (pintype "passive"))
    )
    (net (code "35") (name "Net-(IC4-C)") (class "Default")
      (node (ref "IC4") (pin "3") (pinfunction "C_3") (pintype "passive"))
      (node (ref "R4") (pin "2") (pinfunction "2_2") (pintype "passive"))
    )
    (net (code "36") (name "Net-(IC5A-L1)") (class "Default")
      (node (ref "IC5") (pin "4") (pinfunction "L1_4") (pintype "passive"))
      (node (ref "L1") (pin "1") (pinfunction "P1_1") (pintype "bidirectional"))
    )
    (net (code "37") (name "Net-(IC5A-L2)") (class "Default")
      (node (ref "IC5") (pin "2") (pinfunction "L2_2") (pintype "passive"))
      (node (ref "L1") (pin "2") (pinfunction "P2_2") (pintype "bidirectional"))
    )
    (net (code "38") (name "Net-(IC6-PROG1)") (class "Default")
      (node (ref "IC6") (pin "13") (pinfunction "PROG1_13") (pintype "bidirectional"))
      (node (ref "R10") (pin "1") (pinfunction "1_1") (pintype "passive"))
    )
    (net (code "39") (name "Net-(IC6-PROG3)") (class "Default")
      (node (ref "IC6") (pin "12") (pinfunction "PROG3_12") (pintype "bidirectional"))
      (node (ref "R9") (pin "1") (pinfunction "1_1") (pintype "passive"))
    )
    (net (code "40") (name "Net-(IC6-THERM)") (class "Default")
      (node (ref "IC6") (pin "5") (pinfunction "THERM_5") (pintype "bidirectional"))
      (node (ref "R11") (pin "1") (pinfunction "1_1") (pintype "passive"))
    )
    (net (code "41") (name "Net-(LED2-BLUE_A)") (class "Default")
      (node (ref "LED2") (pin "3") (pinfunction "BLUE_A_3") (pintype "bidirectional"))
      (node (ref "R19") (pin "1") (pinfunction "1_1") (pintype "passive"))
    )
    (net (code "42") (name "Net-(LED2-GREEN_A)") (class "Default")
      (node (ref "LED2") (pin "1") (pinfunction "GREEN_A_1") (pintype "bidirectional"))
      (node (ref "R18") (pin "1") (pinfunction "1_1") (pintype "passive"))
    )
    (net (code "43") (name "Net-(LED2-RED_A)") (class "Default")
      (node (ref "LED2") (pin "2") (pinfunction "RED_A_2") (pintype "bidirectional"))
      (node (ref "R17") (pin "1") (pinfunction "1_1") (pintype "passive"))
    )
    (net (code "44") (name "Net-(Q3-D)") (class "Default")
      (node (ref "Q3") (pin "3") (pinfunction "D_3") (pintype "passive"))
      (node (ref "R12") (pin "1") (pinfunction "1_1") (pintype "passive"))
    )
    (net (code "45") (name "Net-(Q3-G)") (class "Default")
      (node (ref "Q3") (pin "1") (pinfunction "G_1") (pintype "passive"))
      (node (ref "Q4") (pin "3") (pinfunction "D_3") (pintype "bidirectional"))
      (node (ref "R14") (pin "2") (pinfunction "2_2") (pintype "passive"))
    )
    (net (code "46") (name "Net-(R16-Pad2)") (class "Default")
      (node (ref "R16") (pin "2") (pinfunction "2_2") (pintype "passive"))
      (node (ref "USB1") (pin "2") (pinfunction "2_2") (pintype "input"))
    )
    (net (code "47") (name "Net-(X2-SIGNAL)") (class "Default")
      (node (ref "IC2") (pin "ANT") (pinfunction "ANT_ANT") (pintype "output"))
      (node (ref "X2") (pin "SIG") (pinfunction "SIGNAL_SIG") (pintype "bidirectional"))
    )
    (net (code "48") (name "RESET") (class "Default")
      (node (ref "IC3") (pin "17") (pinfunction "RESET_17") (pintype "bidirectional"))
      (node (ref "R2") (pin "1") (pinfunction "1_1") (pintype "passive"))
      (node (ref "S2") (pin "3") (pinfunction "S_3") (pintype "passive"))
      (node (ref "S2") (pin "4") (pinfunction "S_4") (pintype "passive"))
      (node (ref "S3") (pin "P$4") (pinfunction "4_P$4") (pintype "bidirectional"))
    )
    (net (code "49") (name "RF-GPIO0") (class "Default")
      (node (ref "IC2") (pin "GPIO0") (pinfunction "GPIO0_GPIO0") (pintype "bidirectional"))
      (node (ref "IC3") (pin "58") (pinfunction "P0[20]/DTR1/SCL1_58") (pintype "bidirectional"))
    )
    (net (code "50") (name "RF-NIRQ") (class "Default")
      (node (ref "IC2") (pin "NIRQ") (pinfunction "NIRQ_NIRQ") (pintype "output"))
      (node (ref "IC3") (pin "59") (pinfunction "P0[19]/DSR1/SDA1_59") (pintype "bidirectional"))
    )
    (net (code "51") (name "RF-NSEL") (class "Default")
      (node (ref "IC2") (pin "NSEL") (pinfunction "NSEL_NSEL") (pintype "input"))
      (node (ref "IC3") (pin "63") (pinfunction "P0[16]/RXD1/SSEL0/SSEL_63") (pintype "bidirectional"))
    )
    (net (code "52") (name "RF-SCLK") (class "Default")
      (node (ref "IC2") (pin "SCLK") (pinfunction "SCLK_SCLK") (pintype "input"))
      (node (ref "IC3") (pin "62") (pinfunction "P0[15]/TXD1/SCK0/SCK_62") (pintype "bidirectional"))
    )
    (net (code "53") (name "RF-SDI") (class "Default")
      (node (ref "IC2") (pin "SDI") (pinfunction "SDI_SDI") (pintype "bidirectional"))
      (node (ref "IC3") (pin "60") (pinfunction "P0[18]/DCD1/MOSI0/MOSI_60") (pintype "bidirectional"))
    )
    (net (code "54") (name "RF-SDN") (class "Default")
      (node (ref "IC2") (pin "SDN") (pinfunction "SDN_SDN") (pintype "input"))
      (node (ref "IC3") (pin "65") (pinfunction "P2[8]/TD2/TXD2/ENET_MDC_65") (pintype "bidirectional"))
    )
    (net (code "55") (name "RF-SDO") (class "Default")
      (node (ref "IC2") (pin "SDO") (pinfunction "SDO_SDO") (pintype "output"))
      (node (ref "IC3") (pin "61") (pinfunction "P0[17]/CTS1/MISO0/MISO_61") (pintype "bidirectional"))
    )
    (net (code "56") (name "RX") (class "Default")
      (node (ref "IC3") (pin "99") (pinfunction "P0[3]/RXD0/AD0[6]_99") (pintype "bidirectional"))
      (node (ref "S3") (pin "P$5") (pinfunction "5_P$5") (pintype "bidirectional"))
      (node (ref "TP2") (pin "TP") (pinfunction "TP_TP") (pintype "input"))
    )
    (net (code "57") (name "SCL-EXT") (class "Default")
      (node (ref "IC3") (pin "24") (pinfunction "P0[28]/SCL0/USB_SCL_24") (pintype "bidirectional"))
      (node (ref "S3") (pin "P$3") (pinfunction "3_P$3") (pintype "bidirectional"))
    )
    (net (code "58") (name "SDA-EXT") (class "Default")
      (node (ref "IC3") (pin "25") (pinfunction "P0[27]/SDA0/USB_SDA_25") (pintype "bidirectional"))
      (node (ref "S3") (pin "P$2") (pinfunction "2_P$2") (pintype "bidirectional"))
    )
    (net (code "59") (name "TX") (class "Default")
      (node (ref "IC3") (pin "98") (pinfunction "P0[2]/TXD0/AD0[7]_98") (pintype "bidirectional"))
      (node (ref "S3") (pin "P$6") (pinfunction "6_P$6") (pintype "bidirectional"))
      (node (ref "TP1") (pin "TP") (pinfunction "TP_TP") (pintype "input"))
    )
    (net (code "60") (name "USB-CABLE-D+") (class "Default")
      (node (ref "R15") (pin "2") (pinfunction "2_2") (pintype "passive"))
      (node (ref "R4") (pin "1") (pinfunction "1_1") (pintype "passive"))
      (node (ref "USB1") (pin "3") (pinfunction "3_3") (pintype "input"))
    )
    (net (code "61") (name "USB-D+") (class "Default")
      (node (ref "C22") (pin "1") (pinfunction "1_1") (pintype "passive"))
      (node (ref "IC3") (pin "29") (pinfunction "P0[29]/USB_DPLUS_29") (pintype "bidirectional"))
      (node (ref "R15") (pin "1") (pinfunction "1_1") (pintype "passive"))
    )
    (net (code "62") (name "USB-D-") (class "Default")
      (node (ref "C23") (pin "1") (pinfunction "1_1") (pintype "passive"))
      (node (ref "IC3") (pin "30") (pinfunction "P0[30]/USB_DMINUS_30") (pintype "bidirectional"))
      (node (ref "R16") (pin "1") (pinfunction "1_1") (pintype "passive"))
    )
    (net (code "63") (name "V+") (class "Default")
      (node (ref "C9") (pin "1") (pinfunction "1_1") (pintype "passive"))
      (node (ref "IC6") (pin "14") (pinfunction "VBAT_14") (pintype "bidirectional"))
      (node (ref "IC6") (pin "15") (pinfunction "VBAT2_15") (pintype "bidirectional"))
      (node (ref "IC6") (pin "16") (pinfunction "VBAT_SENSE_16") (pintype "bidirectional"))
      (node (ref "Q3") (pin "2") (pinfunction "S_2") (pintype "passive"))
      (node (ref "R14") (pin "1") (pinfunction "1_1") (pintype "passive"))
      (node (ref "SJ1") (pin "2") (pinfunction "2_2") (pintype "passive"))
    )
    (net (code "64") (name "VCC") (class "Default")
      (node (ref "C10") (pin "1") (pinfunction "1_1") (pintype "passive"))
      (node (ref "C24") (pin "1") (pinfunction "1_1") (pintype "passive"))
      (node (ref "C7") (pin "1") (pinfunction "1_1") (pintype "passive"))
      (node (ref "IC5") (pin "5") (pinfunction "VIN_5") (pintype "input"))
      (node (ref "IC5") (pin "6") (pinfunction "EN_6") (pintype "input"))
      (node (ref "IC5") (pin "8") (pinfunction "VINA_8") (pintype "input"))
      (node (ref "IC6") (pin "1") (pinfunction "OUT_1") (pintype "power_in"))
      (node (ref "IC6") (pin "20") (pinfunction "OUT2_20") (pintype "power_in"))
    )
    (net (code "65") (name "VDD") (class "Default")
      (node (ref "C11") (pin "1") (pinfunction "1_1") (pintype "passive"))
      (node (ref "IC1") (pin "12") (pinfunction "3V3_12") (pintype "bidirectional"))
      (node (ref "Q5") (pin "3") (pinfunction "D_3") (pintype "passive"))
    )
    (net (code "66") (name "VEE") (class "Default")
      (node (ref "C1") (pin "1") (pinfunction "1_1") (pintype "passive"))
      (node (ref "C13") (pin "+") (pinfunction "+_+") (pintype "passive"))
      (node (ref "IC2") (pin "VCC") (pinfunction "VCC_VCC") (pintype "power_in"))
      (node (ref "Q6") (pin "3") (pinfunction "D_3") (pintype "passive"))
    )
    (net (code "67") (name "unconnected-(IC1-AIO0-Pad9)") (class "Default")
      (node (ref "IC1") (pin "9") (pinfunction "AIO0_9") (pintype "bidirectional"))
    )
    (net (code "68") (name "unconnected-(IC1-AIO1-Pad10)") (class "Default")
      (node (ref "IC1") (pin "10") (pinfunction "AIO1_10") (pintype "bidirectional"))
    )
    (net (code "69") (name "unconnected-(IC1-CLK-Pad19)") (class "Default")
      (node (ref "IC1") (pin "19") (pinfunction "CLK_19") (pintype "bidirectional"))
    )
    (net (code "70") (name "unconnected-(IC1-CSB-Pad16)") (class "Default")
      (node (ref "IC1") (pin "16") (pinfunction "CSB_16") (pintype "bidirectional"))
    )
    (net (code "71") (name "unconnected-(IC1-CTS-Pad3)") (class "Default")
      (node (ref "IC1") (pin "3") (pinfunction "CTS_3") (pintype "bidirectional"))
    )
    (net (code "72") (name "unconnected-(IC1-MISO-Pad18)") (class "Default")
      (node (ref "IC1") (pin "18") (pinfunction "MISO_18") (pintype "bidirectional"))
    )
    (net (code "73") (name "unconnected-(IC1-MOSI-Pad17)") (class "Default")
      (node (ref "IC1") (pin "17") (pinfunction "MOSI_17") (pintype "bidirectional"))
    )
    (net (code "74") (name "unconnected-(IC1-NC-Pad14)") (class "Default")
      (node (ref "IC1") (pin "14") (pinfunction "NC_14") (pintype "bidirectional"))
    )
    (net (code "75") (name "unconnected-(IC1-PCM_CLK-Pad5)") (class "Default")
      (node (ref "IC1") (pin "5") (pinfunction "PCM_CLK_5") (pintype "bidirectional"))
    )
    (net (code "76") (name "unconnected-(IC1-PCM_IN-Pad7)") (class "Default")
      (node (ref "IC1") (pin "7") (pinfunction "PCM_IN_7") (pintype "bidirectional"))
    )
    (net (code "77") (name "unconnected-(IC1-PCM_OUT-Pad6)") (class "Default")
      (node (ref "IC1") (pin "6") (pinfunction "PCM_OUT_6") (pintype "bidirectional"))
    )
    (net (code "78") (name "unconnected-(IC1-PCN_SYNC-Pad8)") (class "Default")
      (node (ref "IC1") (pin "8") (pinfunction "PCN_SYNC_8") (pintype "bidirectional"))
    )
    (net (code "79") (name "unconnected-(IC1-PIO0-Pad23)") (class "Default")
      (node (ref "IC1") (pin "23") (pinfunction "PIO0_23") (pintype "bidirectional"))
    )
    (net (code "80") (name "unconnected-(IC1-PIO1-Pad24)") (class "Default")
      (node (ref "IC1") (pin "24") (pinfunction "PIO1_24") (pintype "bidirectional"))
    )
    (net (code "81") (name "unconnected-(IC1-PIO2-Pad25)") (class "Default")
      (node (ref "IC1") (pin "25") (pinfunction "PIO2_25") (pintype "bidirectional"))
    )
    (net (code "82") (name "unconnected-(IC1-PIO3-Pad26)") (class "Default")
      (node (ref "IC1") (pin "26") (pinfunction "PIO3_26") (pintype "bidirectional"))
    )
    (net (code "83") (name "unconnected-(IC1-PIO4-Pad27)") (class "Default")
      (node (ref "IC1") (pin "27") (pinfunction "PIO4_27") (pintype "bidirectional"))
    )
    (net (code "84") (name "unconnected-(IC1-PIO5-Pad28)") (class "Default")
      (node (ref "IC1") (pin "28") (pinfunction "PIO5_28") (pintype "bidirectional"))
    )
    (net (code "85") (name "unconnected-(IC1-PIO6-Pad29)") (class "Default")
      (node (ref "IC1") (pin "29") (pinfunction "PIO6_29") (pintype "bidirectional"))
    )
    (net (code "86") (name "unconnected-(IC1-PIO7-Pad30)") (class "Default")
      (node (ref "IC1") (pin "30") (pinfunction "PIO7_30") (pintype "bidirectional"))
    )
    (net (code "87") (name "unconnected-(IC1-PIO8-Pad31)") (class "Default")
      (node (ref "IC1") (pin "31") (pinfunction "PIO8_31") (pintype "bidirectional"))
    )
    (net (code "88") (name "unconnected-(IC1-PIO10-Pad33)") (class "Default")
      (node (ref "IC1") (pin "33") (pinfunction "PIO10_33") (pintype "bidirectional"))
    )
    (net (code "89") (name "unconnected-(IC1-RTS-Pad4)") (class "Default")
      (node (ref "IC1") (pin "4") (pinfunction "RTS_4") (pintype "bidirectional"))
    )
    (net (code "90") (name "unconnected-(IC1-VBUSD+-Pad20)") (class "Default")
      (node (ref "IC1") (pin "20") (pinfunction "VBUSD+_20") (pintype "bidirectional"))
    )
    (net (code "91") (name "unconnected-(IC1-VBUSD--Pad15)") (class "Default")
      (node (ref "IC1") (pin "15") (pinfunction "VBUSD-_15") (pintype "bidirectional"))
    )
    (net (code "92") (name "unconnected-(IC2-PadGPIO1)") (class "Default")
      (node (ref "IC2") (pin "GPIO1") (pinfunction "GPIO1_GPIO1") (pintype "bidirectional"))
    )
    (net (code "93") (name "unconnected-(IC2-PadNC)") (class "Default")
      (node (ref "IC2") (pin "NC") (pinfunction "NC_NC") (pintype "no_connect"))
    )
    (net (code "94") (name "unconnected-(IC3-NC-Pad13)") (class "Default")
      (node (ref "IC3") (pin "13") (pinfunction "NC_13") (pintype "bidirectional"))
    )
    (net (code "95") (name "unconnected-(IC3-P0[4]{slash}I2SRX_CLK{slash}RD2{slash}CAP2[0]-Pad81)") (class "Default")
      (node (ref "IC3") (pin "81") (pinfunction "P0[4]/I2SRX_CLK/RD2/CAP2[0]_81") (pintype "bidirectional"))
    )
    (net (code "96") (name "unconnected-(IC3-P0[5]{slash}I2SRX_WS{slash}TD2{slash}CAP2[1]-Pad80)") (class "Default")
      (node (ref "IC3") (pin "80") (pinfunction "P0[5]/I2SRX_WS/TD2/CAP2[1]_80") (pintype "bidirectional"))
    )
    (net (code "97") (name "unconnected-(IC3-P0[6]{slash}I2SRX_SDA{slash}SSEL1{slash}MAT2[0]-Pad79)") (class "Default")
      (node (ref "IC3") (pin "79") (pinfunction "P0[6]/I2SRX_SDA/SSEL1/MAT2[0]_79") (pintype "bidirectional"))
    )
    (net (code "98") (name "unconnected-(IC3-P0[7]{slash}I2STX_CLK{slash}SCK1{slash}MAT2[1]-Pad78)") (class "Default")
      (node (ref "IC3") (pin "78") (pinfunction "P0[7]/I2STX_CLK/SCK1/MAT2[1]_78") (pintype "bidirectional"))
    )
    (net (code "99") (name "unconnected-(IC3-P0[10]{slash}TXD2{slash}SDA2{slash}MAT3[0]-Pad48)") (class "Default")
      (node (ref "IC3") (pin "48") (pinfunction "P0[10]/TXD2/SDA2/MAT3[0]_48") (pintype "bidirectional"))
    )
    (net (code "100") (name "unconnected-(IC3-P0[11]{slash}RXD2{slash}SCL2{slash}MAT3[1]-Pad49)") (class "Default")
      (node (ref "IC3") (pin "49") (pinfunction "P0[11]/RXD2/SCL2/MAT3[1]_49") (pintype "bidirectional"))
    )
    (net (code "101") (name "unconnected-(IC3-P1[0]{slash}ENET_TXD0-Pad95)") (class "Default")
      (node (ref "IC3") (pin "95") (pinfunction "P1[0]/ENET_TXD0_95") (pintype "bidirectional"))
    )
    (net (code "102") (name "unconnected-(IC3-P1[1]{slash}ENET_TXD1-Pad94)") (class "Default")
      (node (ref "IC3") (pin "94") (pinfunction "P1[1]/ENET_TXD1_94") (pintype "bidirectional"))
    )
    (net (code "103") (name "unconnected-(IC3-P1[4]{slash}ENET_TX_EN-Pad93)") (class "Default")
      (node (ref "IC3") (pin "93") (pinfunction "P1[4]/ENET_TX_EN_93") (pintype "bidirectional"))
    )
    (net (code "104") (name "unconnected-(IC3-P1[8]{slash}ENET_CRS-Pad92)") (class "Default")
      (node (ref "IC3") (pin "92") (pinfunction "P1[8]/ENET_CRS_92") (pintype "bidirectional"))
    )
    (net (code "105") (name "unconnected-(IC3-P1[9]{slash}ENET_RXD0-Pad91)") (class "Default")
      (node (ref "IC3") (pin "91") (pinfunction "P1[9]/ENET_RXD0_91") (pintype "bidirectional"))
    )
    (net (code "106") (name "unconnected-(IC3-P1[10]{slash}ENET_RXD1-Pad90)") (class "Default")
      (node (ref "IC3") (pin "90") (pinfunction "P1[10]/ENET_RXD1_90") (pintype "bidirectional"))
    )
    (net (code "107") (name "unconnected-(IC3-P1[14]{slash}ENET_RX_ER-Pad89)") (class "Default")
      (node (ref "IC3") (pin "89") (pinfunction "P1[14]/ENET_RX_ER_89") (pintype "bidirectional"))
    )
    (net (code "108") (name "unconnected-(IC3-P1[15]{slash}ENET_REF_CLK-Pad88)") (class "Default")
      (node (ref "IC3") (pin "88") (pinfunction "P1[15]/ENET_REF_CLK_88") (pintype "bidirectional"))
    )
    (net (code "109") (name "unconnected-(IC3-P1[16]{slash}ENET_MDC-Pad87)") (class "Default")
      (node (ref "IC3") (pin "87") (pinfunction "P1[16]/ENET_MDC_87") (pintype "bidirectional"))
    )
    (net (code "110") (name "unconnected-(IC3-P1[19]{slash}MCOA0{slash}USB_PPWR{slash}CAP1[1]-Pad33)") (class "Default")
      (node (ref "IC3") (pin "33") (pinfunction "P1[19]/MCOA0/USB_PPWR/CAP1[1]_33") (pintype "bidirectional"))
    )
    (net (code "111") (name "unconnected-(IC3-P1[22]{slash}MCOB0{slash}USB_PWRD{slash}MAT1[0]-Pad36)") (class "Default")
      (node (ref "IC3") (pin "36") (pinfunction "P1[22]/MCOB0/USB_PWRD/MAT1[0]_36") (pintype "bidirectional"))
    )
    (net (code "112") (name "unconnected-(IC3-P1[23]{slash}MCI1{slash}PWM1[4]{slash}MISO0-Pad37)") (class "Default")
      (node (ref "IC3") (pin "37") (pinfunction "P1[23]/MCI1/PWM1[4]/MISO0_37") (pintype "bidirectional"))
    )
    (net (code "113") (name "unconnected-(IC3-P1[24]{slash}MCI2{slash}PWM1[5]{slash}MOSI0-Pad38)") (class "Default")
      (node (ref "IC3") (pin "38") (pinfunction "P1[24]/MCI2/PWM1[5]/MOSI0_38") (pintype "bidirectional"))
    )
    (net (code "114") (name "unconnected-(IC3-P1[25]{slash}MCOA1{slash}MAT1[1]-Pad39)") (class "Default")
      (node (ref "IC3") (pin "39") (pinfunction "P1[25]/MCOA1/MAT1[1]_39") (pintype "bidirectional"))
    )
    (net (code "115") (name "unconnected-(IC3-P1[26]{slash}MCOB1{slash}PWM1[6]{slash}CAP0[0]-Pad40)") (class "Default")
      (node (ref "IC3") (pin "40") (pinfunction "P1[26]/MCOB1/PWM1[6]/CAP0[0]_40") (pintype "bidirectional"))
    )
    (net (code "116") (name "unconnected-(IC3-P1[27]{slash}CLKOUT{slash}USB_OVRCR{slash}CAP0[1]-Pad43)") (class "Default")
      (node (ref "IC3") (pin "43") (pinfunction "P1[27]/CLKOUT/USB_OVRCR/CAP0[1]_43") (pintype "bidirectional"))
    )
    (net (code "117") (name "unconnected-(IC3-P1[28]{slash}MCOA2{slash}PCAP1[0]{slash}MAT0[0]-Pad44)") (class "Default")
      (node (ref "IC3") (pin "44") (pinfunction "P1[28]/MCOA2/PCAP1[0]/MAT0[0]_44") (pintype "bidirectional"))
    )
    (net (code "118") (name "unconnected-(IC3-P1[29]{slash}MCOB2{slash}PCAP1[1]{slash}MAT0[1]-Pad45)") (class "Default")
      (node (ref "IC3") (pin "45") (pinfunction "P1[29]/MCOB2/PCAP1[1]/MAT0[1]_45") (pintype "bidirectional"))
    )
    (net (code "119") (name "unconnected-(IC3-P1[30]{slash}VBUS{slash}AD0[4]-Pad21)") (class "Default")
      (node (ref "IC3") (pin "21") (pinfunction "P1[30]/VBUS/AD0[4]_21") (pintype "bidirectional"))
    )
    (net (code "120") (name "unconnected-(IC3-P1[31]{slash}SCK1{slash}AD0[5]-Pad20)") (class "Default")
      (node (ref "IC3") (pin "20") (pinfunction "P1[31]/SCK1/AD0[5]_20") (pintype "bidirectional"))
    )
    (net (code "121") (name "unconnected-(IC3-P2[0]{slash}PWM1[1]{slash}TXD1-Pad75)") (class "Default")
      (node (ref "IC3") (pin "75") (pinfunction "P2[0]/PWM1[1]/TXD1_75") (pintype "bidirectional"))
    )
    (net (code "122") (name "unconnected-(IC3-P2[1]{slash}PWM1[2]{slash}RXD1-Pad74)") (class "Default")
      (node (ref "IC3") (pin "74") (pinfunction "P2[1]/PWM1[2]/RXD1_74") (pintype "bidirectional"))
    )
    (net (code "123") (name "unconnected-(IC3-P2[2]{slash}PWM1[3]{slash}CTS1{slash}TRACEDATA[3]-Pad73)") (class "Default")
      (node (ref "IC3") (pin "73") (pinfunction "P2[2]/PWM1[3]/CTS1/TRACEDATA[3]_73") (pintype "bidirectional"))
    )
    (net (code "124") (name "unconnected-(IC3-P2[5]{slash}PWM1[6]{slash}DTR1{slash}TRACEDATA[0]-Pad68)") (class "Default")
      (node (ref "IC3") (pin "68") (pinfunction "P2[5]/PWM1[6]/DTR1/TRACEDATA[0]_68") (pintype "bidirectional"))
    )
    (net (code "125") (name "unconnected-(IC3-P2[6]{slash}PCAP1[0]{slash}RI1{slash}TRACECLK-Pad67)") (class "Default")
      (node (ref "IC3") (pin "67") (pinfunction "P2[6]/PCAP1[0]/RI1/TRACECLK_67") (pintype "bidirectional"))
    )
    (net (code "126") (name "unconnected-(IC3-P2[7]{slash}RD2{slash}RTS1-Pad66)") (class "Default")
      (node (ref "IC3") (pin "66") (pinfunction "P2[7]/RD2/RTS1_66") (pintype "bidirectional"))
    )
    (net (code "127") (name "unconnected-(IC3-P2[13]{slash}EINT3{slash}I2STX_SDA-Pad50)") (class "Default")
      (node (ref "IC3") (pin "50") (pinfunction "P2[13]/EINT3/I2STX_SDA_50") (pintype "bidirectional"))
    )
    (net (code "128") (name "unconnected-(IC3-P4[28]{slash}RX_MCLK{slash}MAT2[0]{slash}TXD3-Pad82)") (class "Default")
      (node (ref "IC3") (pin "82") (pinfunction "P4[28]/RX_MCLK/MAT2[0]/TXD3_82") (pintype "bidirectional"))
    )
    (net (code "129") (name "unconnected-(IC3-P4[29]{slash}TX_MCLK{slash}MAT2[1]{slash}RXD3-Pad85)") (class "Default")
      (node (ref "IC3") (pin "85") (pinfunction "P4[29]/TX_MCLK/MAT2[1]/RXD3_85") (pintype "bidirectional"))
    )
    (net (code "130") (name "unconnected-(IC3-RSTOUT-Pad14)") (class "Default")
      (node (ref "IC3") (pin "14") (pinfunction "RSTOUT_14") (pintype "bidirectional"))
    )
    (net (code "131") (name "unconnected-(IC3-RTCK-Pad100)") (class "Default")
      (node (ref "IC3") (pin "100") (pinfunction "RTCK_100") (pintype "bidirectional"))
    )
    (net (code "132") (name "unconnected-(IC6-{slash}PG-Pad6)") (class "Default")
      (node (ref "IC6") (pin "6") (pinfunction "/PG_6") (pintype "open_collector"))
    )
    (net (code "133") (name "unconnected-(USB1-Pad4)") (class "Default")
      (node (ref "USB1") (pin "4") (pinfunction "4_4") (pintype "input"))
    )
    (net (code "134") (name "{slash}BT-ON") (class "Default")
      (node (ref "IC3") (pin "26") (pinfunction "P3[26]/STCLK/MAT0[1]/PWM1[3]_26") (pintype "bidirectional"))
      (node (ref "Q5") (pin "1") (pinfunction "G_1") (pintype "passive"))
    )
    (net (code "135") (name "{slash}RF-ON") (class "Default")
      (node (ref "IC3") (pin "76") (pinfunction "P0[9]/I2STX_SDA/MOSI1/MAT2[3]_76") (pintype "bidirectional"))
      (node (ref "Q6") (pin "1") (pinfunction "G_1") (pintype "passive"))
    )
  )
)
